# CCM_0022.net
KiCad netlist of a schematic drawn in EAGLE
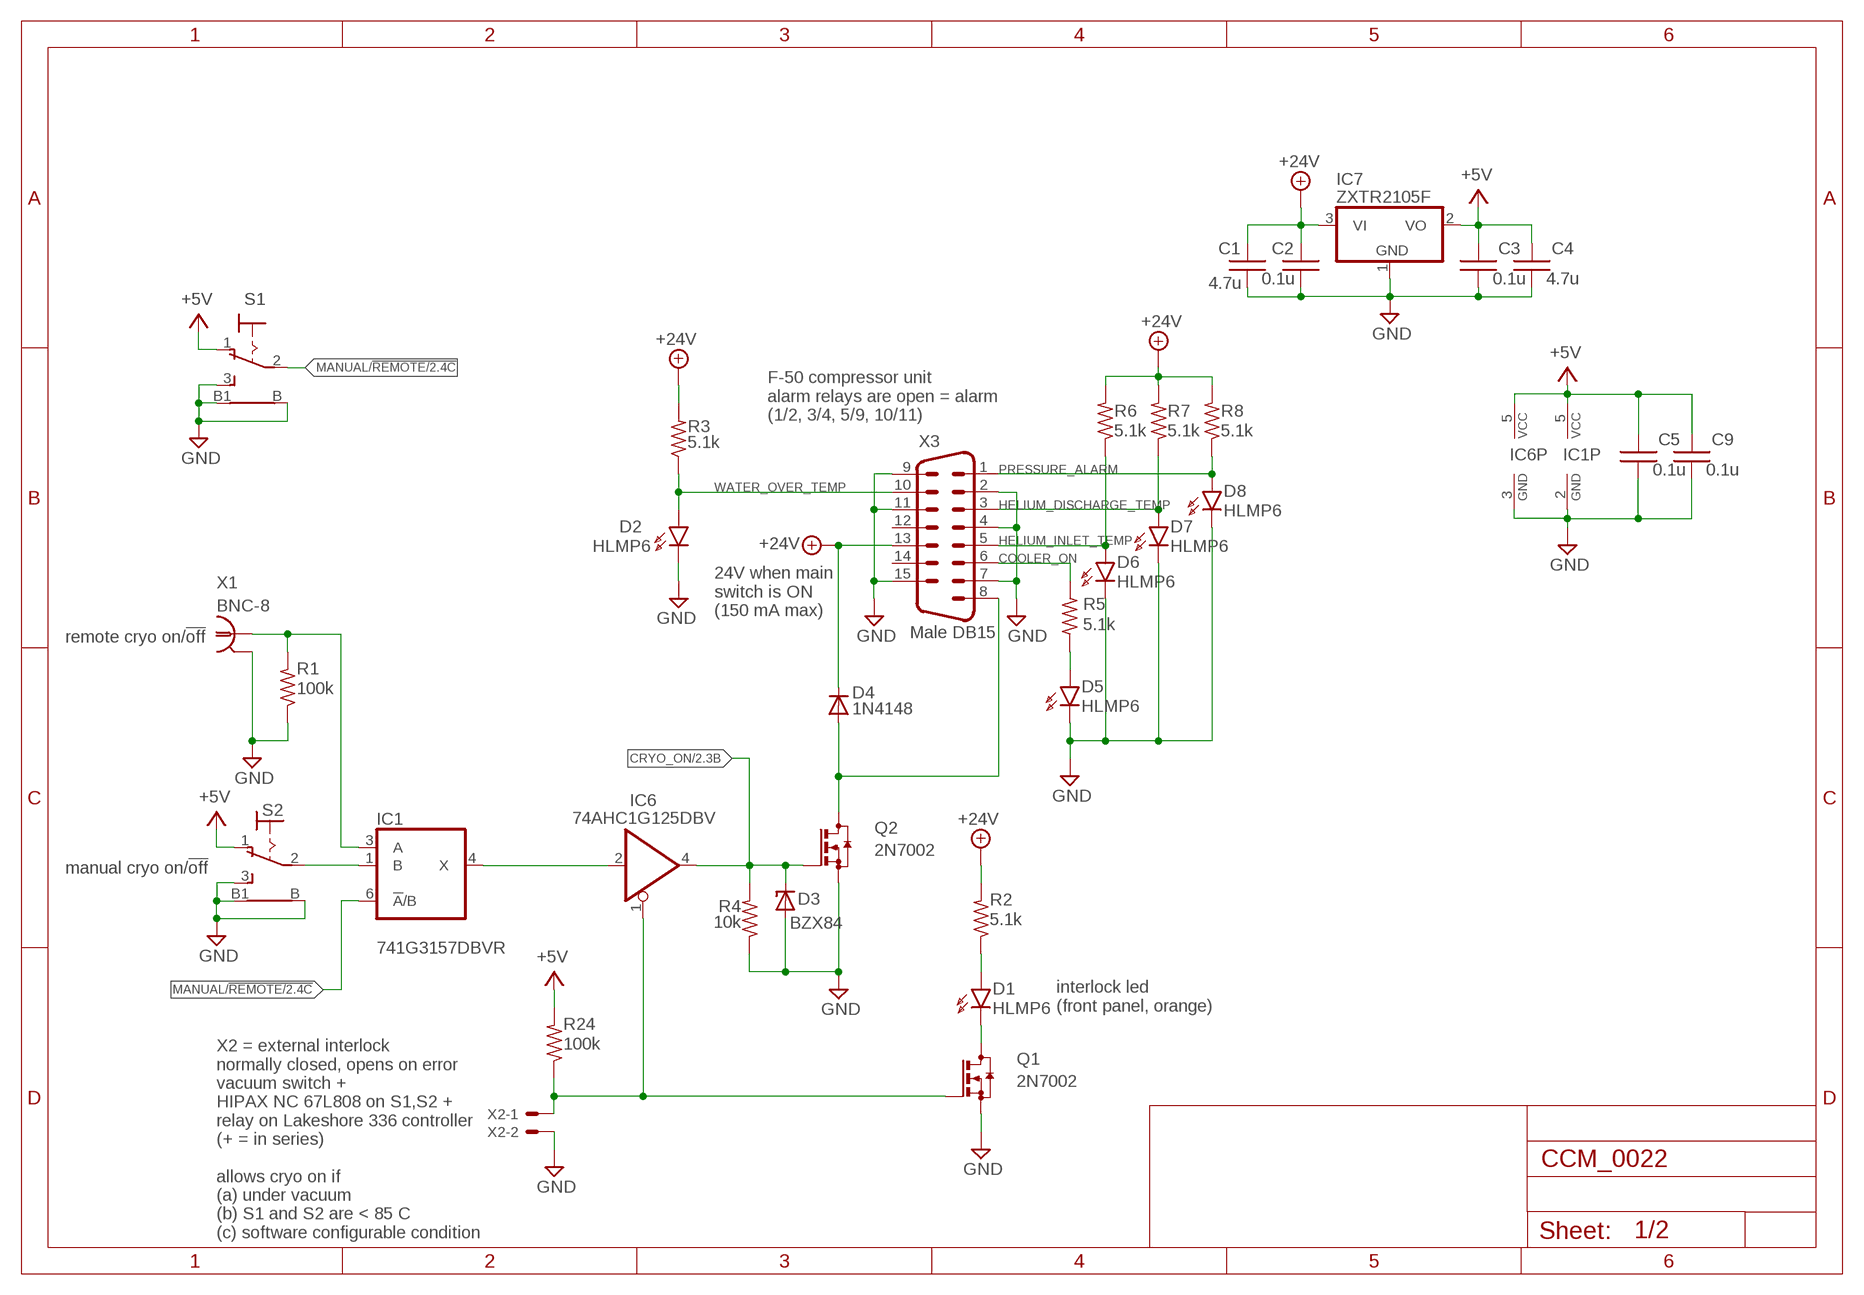
[diagram p0: schematic, sheet 1]
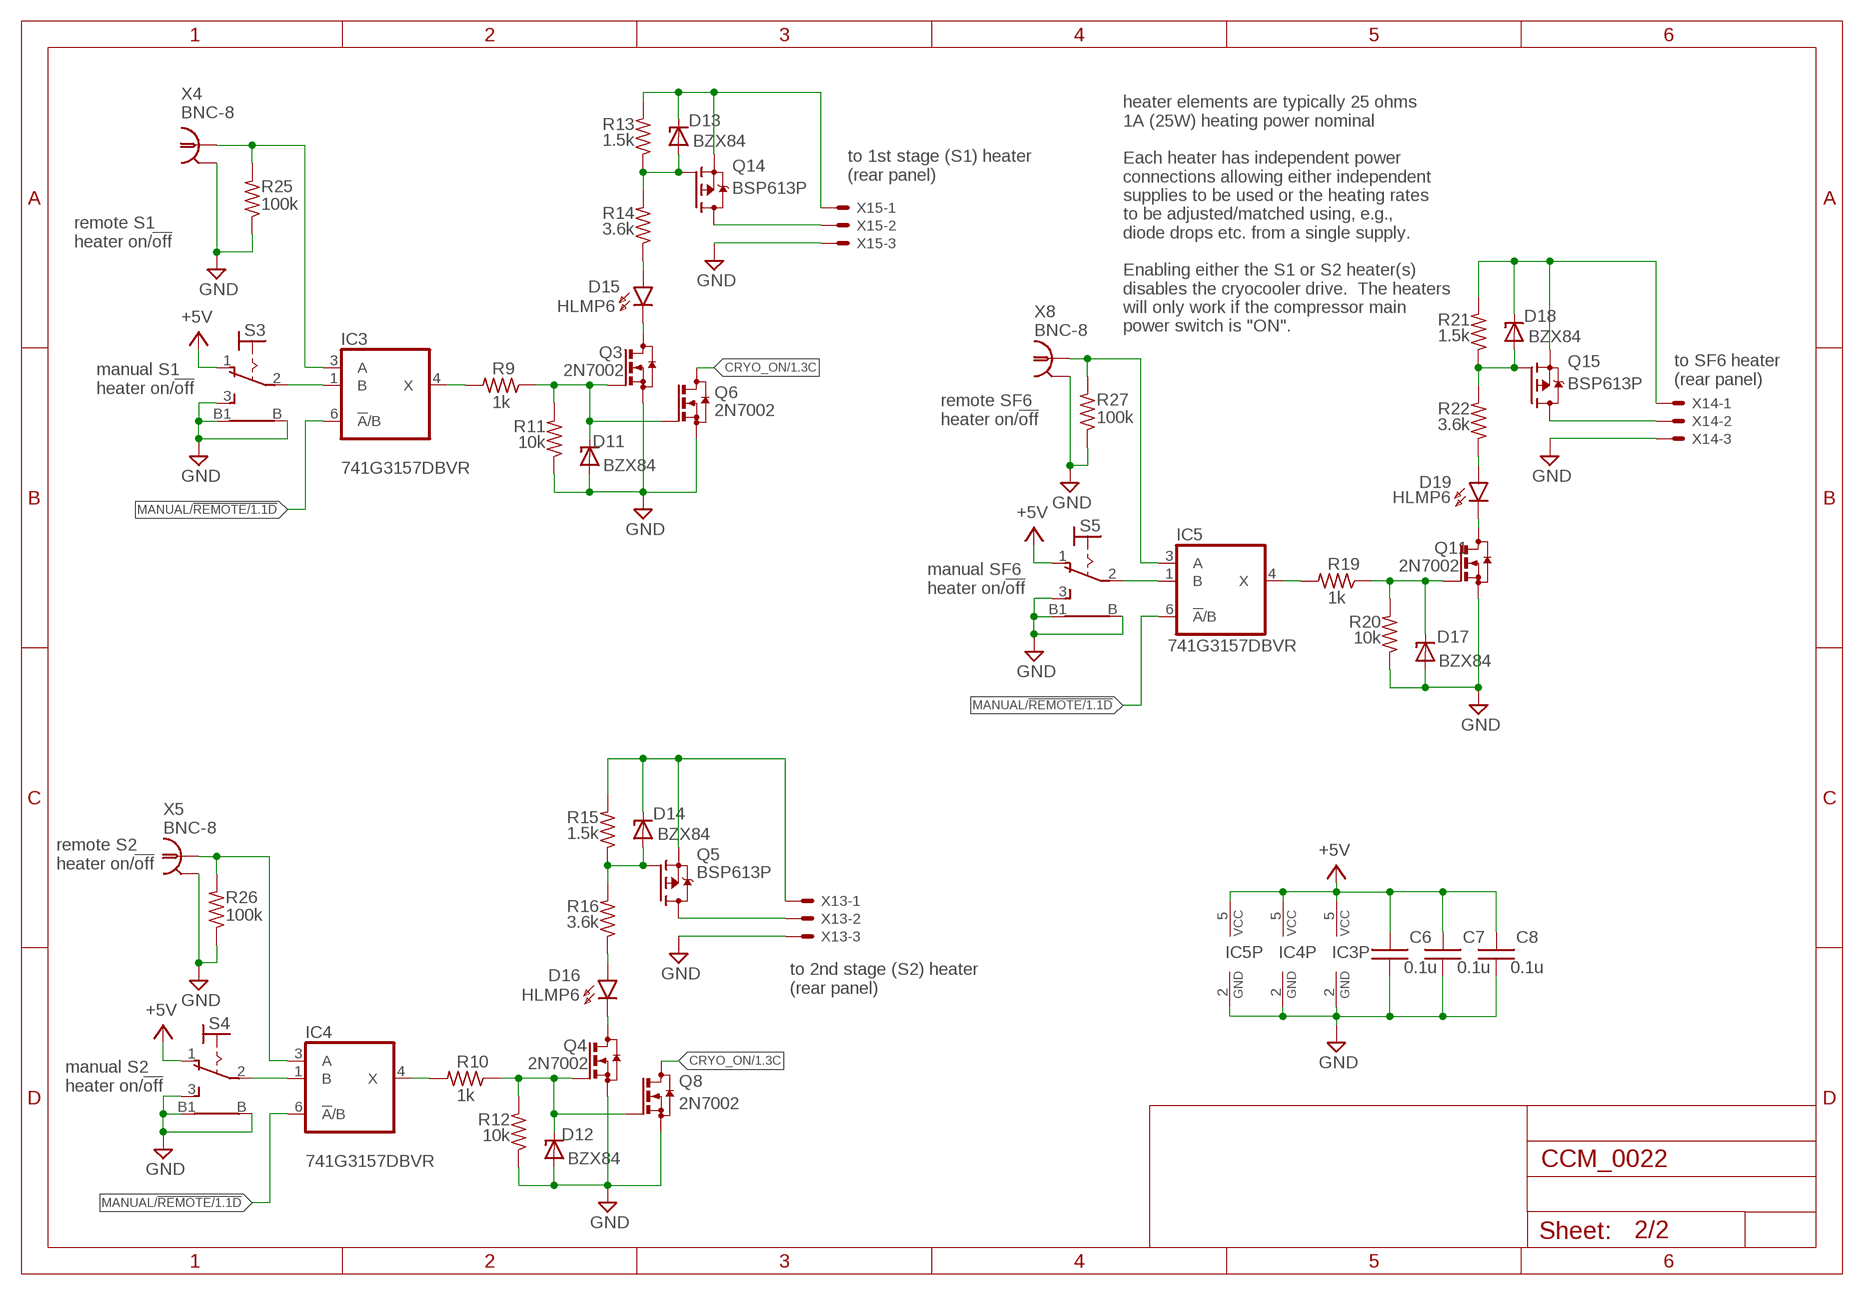
[diagram p1: schematic, sheet 2]

(export (version "E")
  (design (tool "Eeschema 10.0.6"))
  (components
    (comp (ref "C1")
      (value "4.7u")
      (footprint "eagle-import:0603")
      (libsource (lib "eagle-import") (part "CAPACITOR0603"))
    )
    (comp (ref "C2")
      (value "0.1u")
      (footprint "eagle-import:0603")
      (libsource (lib "eagle-import") (part "CAPACITOR0603"))
    )
    (comp (ref "C3")
      (value "0.1u")
      (footprint "eagle-import:0603")
      (libsource (lib "eagle-import") (part "CAPACITOR0603"))
    )
    (comp (ref "C4")
      (value "4.7u")
      (footprint "eagle-import:0603")
      (libsource (lib "eagle-import") (part "CAPACITOR0603"))
    )
    (comp (ref "C5")
      (value "0.1u")
      (footprint "eagle-import:0603")
      (libsource (lib "eagle-import") (part "CAPACITOR0603"))
    )
    (comp (ref "C9")
      (value "0.1u")
      (footprint "eagle-import:0603")
      (libsource (lib "eagle-import") (part "CAPACITOR0603"))
    )
    (comp (ref "D1")
      (value "HLMP6")
      (footprint "eagle-import:HLMP6")
      (fields (field (name "MF") "AGILENT TECHNOLOGIES") (field (name "MPN") "HLMP-6500"))
      (libsource (lib "eagle-import") (part "HLMP6"))
    )
    (comp (ref "D2")
      (value "HLMP6")
      (footprint "eagle-import:HLMP6")
      (fields (field (name "MF") "AGILENT TECHNOLOGIES") (field (name "MPN") "HLMP-6500"))
      (libsource (lib "eagle-import") (part "HLMP6"))
    )
    (comp (ref "D3")
      (value "BZX84")
      (footprint "eagle-import:TO236")
      (libsource (lib "eagle-import") (part "BZX84CSMD"))
    )
    (comp (ref "D4")
      (value "1N4148")
      (footprint "eagle-import:SOD323-W")
      (libsource (lib "eagle-import") (part "DIODE-SOD323-W"))
    )
    (comp (ref "D5")
      (value "HLMP6")
      (footprint "eagle-import:HLMP6")
      (fields (field (name "MF") "AGILENT TECHNOLOGIES") (field (name "MPN") "HLMP-6500"))
      (libsource (lib "eagle-import") (part "HLMP6"))
    )
    (comp (ref "D6")
      (value "HLMP6")
      (footprint "eagle-import:HLMP6")
      (fields (field (name "MF") "AGILENT TECHNOLOGIES") (field (name "MPN") "HLMP-6500"))
      (libsource (lib "eagle-import") (part "HLMP6"))
    )
    (comp (ref "D7")
      (value "HLMP6")
      (footprint "eagle-import:HLMP6")
      (fields (field (name "MF") "AGILENT TECHNOLOGIES") (field (name "MPN") "HLMP-6500"))
      (libsource (lib "eagle-import") (part "HLMP6"))
    )
    (comp (ref "D8")
      (value "HLMP6")
      (footprint "eagle-import:HLMP6")
      (fields (field (name "MF") "AGILENT TECHNOLOGIES") (field (name "MPN") "HLMP-6500"))
      (libsource (lib "eagle-import") (part "HLMP6"))
    )
    (comp (ref "IC1")
      (value "741G3157DBVR")
      (footprint "eagle-import:DBV_R-PDSO-G6")
      (libsource (lib "eagle-import") (part "741G3157DBVR"))
    )
    (comp (ref "IC6")
      (value "74AHC1G125DBV")
      (footprint "eagle-import:SOT23-5")
      (libsource (lib "eagle-import") (part "741G125DBVAHC"))
    )
    (comp (ref "IC7")
      (value "ZXTR2105F")
      (footprint "eagle-import:SOT23")
      (libsource (lib "eagle-import") (part "MCP1703CB"))
    )
    (comp (ref "Q1")
      (value "2N7002")
      (footprint "eagle-import:SOT23")
      (libsource (lib "eagle-import") (part "BSS123"))
    )
    (comp (ref "Q2")
      (value "2N7002")
      (footprint "eagle-import:SOT23")
      (libsource (lib "eagle-import") (part "BSS123"))
    )
    (comp (ref "R1")
      (value "100k")
      (footprint "eagle-import:0603")
      (libsource (lib "eagle-import") (part "R0603"))
    )
    (comp (ref "R2")
      (value "5.1k")
      (footprint "eagle-import:0603")
      (libsource (lib "eagle-import") (part "R0603"))
    )
    (comp (ref "R3")
      (value "5.1k")
      (footprint "eagle-import:0603")
      (libsource (lib "eagle-import") (part "R0603"))
    )
    (comp (ref "R4")
      (value "10k")
      (footprint "eagle-import:0603")
      (libsource (lib "eagle-import") (part "R0603"))
    )
    (comp (ref "R5")
      (value "5.1k")
      (footprint "eagle-import:0603")
      (libsource (lib "eagle-import") (part "R0603"))
    )
    (comp (ref "R6")
      (value "5.1k")
      (footprint "eagle-import:0603")
      (libsource (lib "eagle-import") (part "R0603"))
    )
    (comp (ref "R7")
      (value "5.1k")
      (footprint "eagle-import:0603")
      (libsource (lib "eagle-import") (part "R0603"))
    )
    (comp (ref "R8")
      (value "5.1k")
      (footprint "eagle-import:0603")
      (libsource (lib "eagle-import") (part "R0603"))
    )
    (comp (ref "R24")
      (value "100k")
      (footprint "eagle-import:0603")
      (libsource (lib "eagle-import") (part "R0603"))
    )
    (comp (ref "S1")
      (value "LPV-1")
      (footprint "eagle-import:LPV-1")
      (libsource (lib "eagle-import") (part "LPV-1"))
    )
    (comp (ref "S2")
      (value "LPV-1")
      (footprint "eagle-import:LPV-1")
      (libsource (lib "eagle-import") (part "LPV-1"))
    )
    (comp (ref "X1")
      (value "BNC-8")
      (footprint "eagle-import:BNC_RA")
      (libsource (lib "eagle-import") (part "BNC-8"))
    )
    (comp (ref "X2")
      (value "22-23-2021")
      (footprint "eagle-import:22-23-2021")
      (fields (field (name "MF") "MOLEX"))
      (libsource (lib "eagle-import") (part "22-23-2021"))
    )
    (comp (ref "X3")
      (value "Male DB15")
      (footprint "eagle-import:M15HP")
      (libsource (lib "eagle-import") (part "M15HP"))
    )
    (comp (ref "C6")
      (value "0.1u")
      (footprint "eagle-import:0603")
      (libsource (lib "eagle-import") (part "CAPACITOR0603"))
    )
    (comp (ref "C7")
      (value "0.1u")
      (footprint "eagle-import:0603")
      (libsource (lib "eagle-import") (part "CAPACITOR0603"))
    )
    (comp (ref "C8")
      (value "0.1u")
      (footprint "eagle-import:0603")
      (libsource (lib "eagle-import") (part "CAPACITOR0603"))
    )
    (comp (ref "D11")
      (value "BZX84")
      (footprint "eagle-import:TO236")
      (libsource (lib "eagle-import") (part "BZX84CSMD"))
    )
    (comp (ref "D12")
      (value "BZX84")
      (footprint "eagle-import:TO236")
      (libsource (lib "eagle-import") (part "BZX84CSMD"))
    )
    (comp (ref "D13")
      (value "BZX84")
      (footprint "eagle-import:TO236")
      (libsource (lib "eagle-import") (part "BZX84CSMD"))
    )
    (comp (ref "D14")
      (value "BZX84")
      (footprint "eagle-import:TO236")
      (libsource (lib "eagle-import") (part "BZX84CSMD"))
    )
    (comp (ref "D15")
      (value "HLMP6")
      (footprint "eagle-import:HLMP6")
      (fields (field (name "MF") "AGILENT TECHNOLOGIES") (field (name "MPN") "HLMP-6500"))
      (libsource (lib "eagle-import") (part "HLMP6"))
    )
    (comp (ref "D16")
      (value "HLMP6")
      (footprint "eagle-import:HLMP6")
      (fields (field (name "MF") "AGILENT TECHNOLOGIES") (field (name "MPN") "HLMP-6500"))
      (libsource (lib "eagle-import") (part "HLMP6"))
    )
    (comp (ref "D17")
      (value "BZX84")
      (footprint "eagle-import:TO236")
      (libsource (lib "eagle-import") (part "BZX84CSMD"))
    )
    (comp (ref "D18")
      (value "BZX84")
      (footprint "eagle-import:TO236")
      (libsource (lib "eagle-import") (part "BZX84CSMD"))
    )
    (comp (ref "D19")
      (value "HLMP6")
      (footprint "eagle-import:HLMP6")
      (fields (field (name "MF") "AGILENT TECHNOLOGIES") (field (name "MPN") "HLMP-6500"))
      (libsource (lib "eagle-import") (part "HLMP6"))
    )
    (comp (ref "IC3")
      (value "741G3157DBVR")
      (footprint "eagle-import:DBV_R-PDSO-G6")
      (libsource (lib "eagle-import") (part "741G3157DBVR"))
    )
    (comp (ref "IC4")
      (value "741G3157DBVR")
      (footprint "eagle-import:DBV_R-PDSO-G6")
      (libsource (lib "eagle-import") (part "741G3157DBVR"))
    )
    (comp (ref "IC5")
      (value "741G3157DBVR")
      (footprint "eagle-import:DBV_R-PDSO-G6")
      (libsource (lib "eagle-import") (part "741G3157DBVR"))
    )
    (comp (ref "Q3")
      (value "2N7002")
      (footprint "eagle-import:SOT23")
      (libsource (lib "eagle-import") (part "BSS123"))
    )
    (comp (ref "Q4")
      (value "2N7002")
      (footprint "eagle-import:SOT23")
      (libsource (lib "eagle-import") (part "BSS123"))
    )
    (comp (ref "Q5")
      (value "BSP613P")
      (footprint "eagle-import:SOT223")
      (libsource (lib "eagle-import") (part "BSP170P"))
    )
    (comp (ref "Q6")
      (value "2N7002")
      (footprint "eagle-import:SOT23")
      (libsource (lib "eagle-import") (part "BSS123"))
    )
    (comp (ref "Q8")
      (value "2N7002")
      (footprint "eagle-import:SOT23")
      (libsource (lib "eagle-import") (part "BSS123"))
    )
    (comp (ref "Q11")
      (value "2N7002")
      (footprint "eagle-import:SOT23")
      (libsource (lib "eagle-import") (part "BSS123"))
    )
    (comp (ref "Q14")
      (value "BSP613P")
      (footprint "eagle-import:SOT223")
      (libsource (lib "eagle-import") (part "BSP170P"))
    )
    (comp (ref "Q15")
      (value "BSP613P")
      (footprint "eagle-import:SOT223")
      (libsource (lib "eagle-import") (part "BSP170P"))
    )
    (comp (ref "R9")
      (value "1k")
      (footprint "eagle-import:0603")
      (libsource (lib "eagle-import") (part "R0603"))
    )
    (comp (ref "R10")
      (value "1k")
      (footprint "eagle-import:0603")
      (libsource (lib "eagle-import") (part "R0603"))
    )
    (comp (ref "R11")
      (value "10k")
      (footprint "eagle-import:0603")
      (libsource (lib "eagle-import") (part "R0603"))
    )
    (comp (ref "R12")
      (value "10k")
      (footprint "eagle-import:0603")
      (libsource (lib "eagle-import") (part "R0603"))
    )
    (comp (ref "R13")
      (value "1.5k")
      (footprint "eagle-import:0603")
      (libsource (lib "eagle-import") (part "R0603"))
    )
    (comp (ref "R14")
      (value "3.6k")
      (footprint "eagle-import:0603")
      (libsource (lib "eagle-import") (part "R0603"))
    )
    (comp (ref "R15")
      (value "1.5k")
      (footprint "eagle-import:0603")
      (libsource (lib "eagle-import") (part "R0603"))
    )
    (comp (ref "R16")
      (value "3.6k")
      (footprint "eagle-import:0603")
      (libsource (lib "eagle-import") (part "R0603"))
    )
    (comp (ref "R19")
      (value "1k")
      (footprint "eagle-import:0603")
      (libsource (lib "eagle-import") (part "R0603"))
    )
    (comp (ref "R20")
      (value "10k")
      (footprint "eagle-import:0603")
      (libsource (lib "eagle-import") (part "R0603"))
    )
    (comp (ref "R21")
      (value "1.5k")
      (footprint "eagle-import:0603")
      (libsource (lib "eagle-import") (part "R0603"))
    )
    (comp (ref "R22")
      (value "3.6k")
      (footprint "eagle-import:0603")
      (libsource (lib "eagle-import") (part "R0603"))
    )
    (comp (ref "R25")
      (value "100k")
      (footprint "eagle-import:0603")
      (libsource (lib "eagle-import") (part "R0603"))
    )
    (comp (ref "R26")
      (value "100k")
      (footprint "eagle-import:0603")
      (libsource (lib "eagle-import") (part "R0603"))
    )
    (comp (ref "R27")
      (value "100k")
      (footprint "eagle-import:0603")
      (libsource (lib "eagle-import") (part "R0603"))
    )
    (comp (ref "S3")
      (value "LPV-1")
      (footprint "eagle-import:LPV-1")
      (libsource (lib "eagle-import") (part "LPV-1"))
    )
    (comp (ref "S4")
      (value "LPV-1")
      (footprint "eagle-import:LPV-1")
      (libsource (lib "eagle-import") (part "LPV-1"))
    )
    (comp (ref "S5")
      (value "LPV-1")
      (footprint "eagle-import:LPV-1")
      (libsource (lib "eagle-import") (part "LPV-1"))
    )
    (comp (ref "X4")
      (value "BNC-8")
      (footprint "eagle-import:BNC_RA")
      (libsource (lib "eagle-import") (part "BNC-8"))
    )
    (comp (ref "X5")
      (value "BNC-8")
      (footprint "eagle-import:BNC_RA")
      (libsource (lib "eagle-import") (part "BNC-8"))
    )
    (comp (ref "X8")
      (value "BNC-8")
      (footprint "eagle-import:BNC_RA")
      (libsource (lib "eagle-import") (part "BNC-8"))
    )
    (comp (ref "X13")
      (value "22-23-2031")
      (footprint "eagle-import:22-23-2031")
      (fields (field (name "MF") "MOLEX"))
      (libsource (lib "eagle-import") (part "22-23-2031"))
    )
    (comp (ref "X14")
      (value "22-23-2031")
      (footprint "eagle-import:22-23-2031")
      (fields (field (name "MF") "MOLEX"))
      (libsource (lib "eagle-import") (part "22-23-2031"))
    )
    (comp (ref "X15")
      (value "22-23-2031")
      (footprint "eagle-import:22-23-2031")
      (fields (field (name "MF") "MOLEX"))
      (libsource (lib "eagle-import") (part "22-23-2031"))
    )
  )
  (nets
    (net (code "1") (name "+5V") (class "Default")
      (node (ref "C3") (pin "1") (pinfunction "1_1") (pintype "passive"))
      (node (ref "C4") (pin "1") (pinfunction "1_1") (pintype "passive"))
      (node (ref "C5") (pin "1") (pinfunction "1_1") (pintype "passive"))
      (node (ref "C6") (pin "1") (pinfunction "1_1") (pintype "passive"))
      (node (ref "C7") (pin "1") (pinfunction "1_1") (pintype "passive"))
      (node (ref "C8") (pin "1") (pinfunction "1_1") (pintype "passive"))
      (node (ref "C9") (pin "1") (pinfunction "1_1") (pintype "passive"))
      (node (ref "IC1") (pin "5") (pinfunction "VCC_5") (pintype "power_in"))
      (node (ref "IC3") (pin "5") (pinfunction "VCC_5") (pintype "power_in"))
      (node (ref "IC4") (pin "5") (pinfunction "VCC_5") (pintype "power_in"))
      (node (ref "IC5") (pin "5") (pinfunction "VCC_5") (pintype "power_in"))
      (node (ref "IC6") (pin "5") (pinfunction "VCC_5") (pintype "power_in"))
      (node (ref "IC7") (pin "2") (pinfunction "VO_2") (pintype "passive"))
      (node (ref "R24") (pin "2") (pinfunction "2_2") (pintype "passive"))
      (node (ref "S1") (pin "1") (pinfunction "O_1") (pintype "passive"))
      (node (ref "S2") (pin "1") (pinfunction "O_1") (pintype "passive"))
      (node (ref "S3") (pin "1") (pinfunction "O_1") (pintype "passive"))
      (node (ref "S4") (pin "1") (pinfunction "O_1") (pintype "passive"))
      (node (ref "S5") (pin "1") (pinfunction "O_1") (pintype "passive"))
    )
    (net (code "2") (name "+24V") (class "Default")
      (node (ref "C1") (pin "1") (pinfunction "1_1") (pintype "passive"))
      (node (ref "C2") (pin "1") (pinfunction "1_1") (pintype "passive"))
      (node (ref "D4") (pin "C") (pinfunction "C_C") (pintype "passive"))
      (node (ref "IC7") (pin "3") (pinfunction "VI_3") (pintype "input"))
      (node (ref "R2") (pin "2") (pinfunction "2_2") (pintype "passive"))
      (node (ref "R3") (pin "2") (pinfunction "2_2") (pintype "passive"))
      (node (ref "R6") (pin "2") (pinfunction "2_2") (pintype "passive"))
      (node (ref "R7") (pin "2") (pinfunction "2_2") (pintype "passive"))
      (node (ref "R8") (pin "2") (pinfunction "2_2") (pintype "passive"))
      (node (ref "X3") (pin "13") (pinfunction "13_13") (pintype "passive"))
    )
    (net (code "3") (name "COOLER_ON") (class "Default")
      (node (ref "R5") (pin "2") (pinfunction "2_2") (pintype "passive"))
      (node (ref "X3") (pin "6") (pinfunction "6_6") (pintype "passive"))
    )
    (net (code "4") (name "CRYO_ON") (class "Default")
      (node (ref "D3") (pin "C") (pinfunction "C_C") (pintype "passive"))
      (node (ref "IC6") (pin "4") (pinfunction "O_4") (pintype "tri_state"))
      (node (ref "Q2") (pin "1") (pinfunction "G_1") (pintype "passive"))
      (node (ref "Q6") (pin "3") (pinfunction "D_3") (pintype "passive"))
      (node (ref "Q8") (pin "3") (pinfunction "D_3") (pintype "passive"))
      (node (ref "R4") (pin "2") (pinfunction "2_2") (pintype "passive"))
    )
    (net (code "5") (name "GND") (class "Default")
      (node (ref "C1") (pin "2") (pinfunction "2_2") (pintype "passive"))
      (node (ref "C2") (pin "2") (pinfunction "2_2") (pintype "passive"))
      (node (ref "C3") (pin "2") (pinfunction "2_2") (pintype "passive"))
      (node (ref "C4") (pin "2") (pinfunction "2_2") (pintype "passive"))
      (node (ref "C5") (pin "2") (pinfunction "2_2") (pintype "passive"))
      (node (ref "C6") (pin "2") (pinfunction "2_2") (pintype "passive"))
      (node (ref "C7") (pin "2") (pinfunction "2_2") (pintype "passive"))
      (node (ref "C8") (pin "2") (pinfunction "2_2") (pintype "passive"))
      (node (ref "C9") (pin "2") (pinfunction "2_2") (pintype "passive"))
      (node (ref "D11") (pin "A") (pinfunction "A_A") (pintype "passive"))
      (node (ref "D12") (pin "A") (pinfunction "A_A") (pintype "passive"))
      (node (ref "D17") (pin "A") (pinfunction "A_A") (pintype "passive"))
      (node (ref "D2") (pin "K") (pinfunction "K_K") (pintype "passive"))
      (node (ref "D3") (pin "A") (pinfunction "A_A") (pintype "passive"))
      (node (ref "D5") (pin "K") (pinfunction "K_K") (pintype "passive"))
      (node (ref "D6") (pin "K") (pinfunction "K_K") (pintype "passive"))
      (node (ref "D7") (pin "K") (pinfunction "K_K") (pintype "passive"))
      (node (ref "D8") (pin "K") (pinfunction "K_K") (pintype "passive"))
      (node (ref "IC1") (pin "2") (pinfunction "GND_2") (pintype "power_in"))
      (node (ref "IC3") (pin "2") (pinfunction "GND_2") (pintype "power_in"))
      (node (ref "IC4") (pin "2") (pinfunction "GND_2") (pintype "power_in"))
      (node (ref "IC5") (pin "2") (pinfunction "GND_2") (pintype "power_in"))
      (node (ref "IC6") (pin "3") (pinfunction "GND_3") (pintype "power_in"))
      (node (ref "IC7") (pin "1") (pinfunction "GND_1") (pintype "passive"))
      (node (ref "Q1") (pin "2") (pinfunction "S_2") (pintype "passive"))
      (node (ref "Q11") (pin "2") (pinfunction "S_2") (pintype "passive"))
      (node (ref "Q2") (pin "2") (pinfunction "S_2") (pintype "passive"))
      (node (ref "Q3") (pin "2") (pinfunction "S_2") (pintype "passive"))
      (node (ref "Q4") (pin "2") (pinfunction "S_2") (pintype "passive"))
      (node (ref "Q6") (pin "2") (pinfunction "S_2") (pintype "passive"))
      (node (ref "Q8") (pin "2") (pinfunction "S_2") (pintype "passive"))
      (node (ref "R1") (pin "1") (pinfunction "1_1") (pintype "passive"))
      (node (ref "R11") (pin "1") (pinfunction "1_1") (pintype "passive"))
      (node (ref "R12") (pin "1") (pinfunction "1_1") (pintype "passive"))
      (node (ref "R20") (pin "1") (pinfunction "1_1") (pintype "passive"))
      (node (ref "R25") (pin "1") (pinfunction "1_1") (pintype "passive"))
      (node (ref "R26") (pin "1") (pinfunction "1_1") (pintype "passive"))
      (node (ref "R27") (pin "1") (pinfunction "1_1") (pintype "passive"))
      (node (ref "R4") (pin "1") (pinfunction "1_1") (pintype "passive"))
      (node (ref "S1") (pin "3") (pinfunction "S_3") (pintype "passive"))
      (node (ref "S1") (pin "B") (pinfunction "B_B") (pintype "passive"))
      (node (ref "S1") (pin "B1") (pinfunction "B1_B1") (pintype "passive"))
      (node (ref "S2") (pin "3") (pinfunction "S_3") (pintype "passive"))
      (node (ref "S2") (pin "B") (pinfunction "B_B") (pintype "passive"))
      (node (ref "S2") (pin "B1") (pinfunction "B1_B1") (pintype "passive"))
      (node (ref "S3") (pin "3") (pinfunction "S_3") (pintype "passive"))
      (node (ref "S3") (pin "B") (pinfunction "B_B") (pintype "passive"))
      (node (ref "S3") (pin "B1") (pinfunction "B1_B1") (pintype "passive"))
      (node (ref "S4") (pin "3") (pinfunction "S_3") (pintype "passive"))
      (node (ref "S4") (pin "B") (pinfunction "B_B") (pintype "passive"))
      (node (ref "S4") (pin "B1") (pinfunction "B1_B1") (pintype "passive"))
      (node (ref "S5") (pin "3") (pinfunction "S_3") (pintype "passive"))
      (node (ref "S5") (pin "B") (pinfunction "B_B") (pintype "passive"))
      (node (ref "S5") (pin "B1") (pinfunction "B1_B1") (pintype "passive"))
      (node (ref "X1") (pin "2") (pinfunction "2_2") (pintype "passive"))
      (node (ref "X13") (pin "3") (pinfunction "S_3") (pintype "passive"))
      (node (ref "X14") (pin "3") (pinfunction "S_3") (pintype "passive"))
      (node (ref "X15") (pin "3") (pinfunction "S_3") (pintype "passive"))
      (node (ref "X2") (pin "2") (pinfunction "S_2") (pintype "passive"))
      (node (ref "X3") (pin "11") (pinfunction "11_11") (pintype "passive"))
      (node (ref "X3") (pin "15") (pinfunction "15_15") (pintype "passive"))
      (node (ref "X3") (pin "2") (pinfunction "2_2") (pintype "passive"))
      (node (ref "X3") (pin "4") (pinfunction "4_4") (pintype "passive"))
      (node (ref "X3") (pin "7") (pinfunction "7_7") (pintype "passive"))
      (node (ref "X3") (pin "9") (pinfunction "9_9") (pintype "passive"))
      (node (ref "X4") (pin "2") (pinfunction "2_2") (pintype "passive"))
      (node (ref "X5") (pin "2") (pinfunction "2_2") (pintype "passive"))
      (node (ref "X8") (pin "2") (pinfunction "2_2") (pintype "passive"))
    )
    (net (code "6") (name "HELIUM_DISCHARGE_TEMP") (class "Default")
      (node (ref "D7") (pin "A") (pinfunction "A_A") (pintype "passive"))
      (node (ref "R7") (pin "1") (pinfunction "1_1") (pintype "passive"))
      (node (ref "X3") (pin "3") (pinfunction "3_3") (pintype "passive"))
    )
    (net (code "7") (name "HELIUM_INLET_TEMP") (class "Default")
      (node (ref "D6") (pin "A") (pinfunction "A_A") (pintype "passive"))
      (node (ref "R6") (pin "1") (pinfunction "1_1") (pintype "passive"))
      (node (ref "X3") (pin "5") (pinfunction "5_5") (pintype "passive"))
    )
    (net (code "8") (name "MANUAL{slash}~{REMOTE}") (class "Default")
      (node (ref "IC1") (pin "6") (pinfunction "~{A}/B_6") (pintype "input"))
      (node (ref "IC3") (pin "6") (pinfunction "~{A}/B_6") (pintype "input"))
      (node (ref "IC4") (pin "6") (pinfunction "~{A}/B_6") (pintype "input"))
      (node (ref "IC5") (pin "6") (pinfunction "~{A}/B_6") (pintype "input"))
      (node (ref "S1") (pin "2") (pinfunction "P_2") (pintype "passive"))
    )
    (net (code "9") (name "Net-(D1-PadA)") (class "Default")
      (node (ref "D1") (pin "A") (pinfunction "A_A") (pintype "passive"))
      (node (ref "R2") (pin "1") (pinfunction "1_1") (pintype "passive"))
    )
    (net (code "10") (name "Net-(D5-PadA)") (class "Default")
      (node (ref "D5") (pin "A") (pinfunction "A_A") (pintype "passive"))
      (node (ref "R5") (pin "1") (pinfunction "1_1") (pintype "passive"))
    )
    (net (code "11") (name "Net-(D15-PadA)") (class "Default")
      (node (ref "D15") (pin "A") (pinfunction "A_A") (pintype "passive"))
      (node (ref "R14") (pin "1") (pinfunction "1_1") (pintype "passive"))
    )
    (net (code "12") (name "Net-(D16-PadA)") (class "Default")
      (node (ref "D16") (pin "A") (pinfunction "A_A") (pintype "passive"))
      (node (ref "R16") (pin "1") (pinfunction "1_1") (pintype "passive"))
    )
    (net (code "13") (name "Net-(D19-PadA)") (class "Default")
      (node (ref "D19") (pin "A") (pinfunction "A_A") (pintype "passive"))
      (node (ref "R22") (pin "1") (pinfunction "1_1") (pintype "passive"))
    )
    (net (code "14") (name "Net-(IC1A-A)") (class "Default")
      (node (ref "IC1") (pin "3") (pinfunction "A_3") (pintype "bidirectional"))
      (node (ref "R1") (pin "2") (pinfunction "2_2") (pintype "passive"))
      (node (ref "X1") (pin "1") (pinfunction "1_1") (pintype "passive"))
    )
    (net (code "15") (name "Net-(IC1A-B)") (class "Default")
      (node (ref "IC1") (pin "1") (pinfunction "B_1") (pintype "bidirectional"))
      (node (ref "S2") (pin "2") (pinfunction "P_2") (pintype "passive"))
    )
    (net (code "16") (name "Net-(IC1A-X)") (class "Default")
      (node (ref "IC1") (pin "4") (pinfunction "X_4") (pintype "bidirectional"))
      (node (ref "IC6") (pin "2") (pinfunction "I_2") (pintype "input"))
    )
    (net (code "17") (name "Net-(IC3A-A)") (class "Default")
      (node (ref "IC3") (pin "3") (pinfunction "A_3") (pintype "bidirectional"))
      (node (ref "R25") (pin "2") (pinfunction "2_2") (pintype "passive"))
      (node (ref "X4") (pin "1") (pinfunction "1_1") (pintype "passive"))
    )
    (net (code "18") (name "Net-(IC3A-B)") (class "Default")
      (node (ref "IC3") (pin "1") (pinfunction "B_1") (pintype "bidirectional"))
      (node (ref "S3") (pin "2") (pinfunction "P_2") (pintype "passive"))
    )
    (net (code "19") (name "Net-(IC3A-X)") (class "Default")
      (node (ref "IC3") (pin "4") (pinfunction "X_4") (pintype "bidirectional"))
      (node (ref "R9") (pin "2") (pinfunction "2_2") (pintype "passive"))
    )
    (net (code "20") (name "Net-(IC4A-A)") (class "Default")
      (node (ref "IC4") (pin "3") (pinfunction "A_3") (pintype "bidirectional"))
      (node (ref "R26") (pin "2") (pinfunction "2_2") (pintype "passive"))
      (node (ref "X5") (pin "1") (pinfunction "1_1") (pintype "passive"))
    )
    (net (code "21") (name "Net-(IC4A-B)") (class "Default")
      (node (ref "IC4") (pin "1") (pinfunction "B_1") (pintype "bidirectional"))
      (node (ref "S4") (pin "2") (pinfunction "P_2") (pintype "passive"))
    )
    (net (code "22") (name "Net-(IC4A-X)") (class "Default")
      (node (ref "IC4") (pin "4") (pinfunction "X_4") (pintype "bidirectional"))
      (node (ref "R10") (pin "2") (pinfunction "2_2") (pintype "passive"))
    )
    (net (code "23") (name "Net-(IC5A-A)") (class "Default")
      (node (ref "IC5") (pin "3") (pinfunction "A_3") (pintype "bidirectional"))
      (node (ref "R27") (pin "2") (pinfunction "2_2") (pintype "passive"))
      (node (ref "X8") (pin "1") (pinfunction "1_1") (pintype "passive"))
    )
    (net (code "24") (name "Net-(IC5A-B)") (class "Default")
      (node (ref "IC5") (pin "1") (pinfunction "B_1") (pintype "bidirectional"))
      (node (ref "S5") (pin "2") (pinfunction "P_2") (pintype "passive"))
    )
    (net (code "25") (name "Net-(IC5A-X)") (class "Default")
      (node (ref "IC5") (pin "4") (pinfunction "X_4") (pintype "bidirectional"))
      (node (ref "R19") (pin "2") (pinfunction "2_2") (pintype "passive"))
    )
    (net (code "26") (name "Net-(IC6A-OE)") (class "Default")
      (node (ref "IC6") (pin "1") (pinfunction "OE_1") (pintype "input"))
      (node (ref "Q1") (pin "1") (pinfunction "G_1") (pintype "passive"))
      (node (ref "R24") (pin "1") (pinfunction "1_1") (pintype "passive"))
      (node (ref "X2") (pin "1") (pinfunction "S_1") (pintype "passive"))
    )
    (net (code "27") (name "Net-(Q1-D)") (class "Default")
      (node (ref "D1") (pin "K") (pinfunction "K_K") (pintype "passive"))
      (node (ref "Q1") (pin "3") (pinfunction "D_3") (pintype "passive"))
    )
    (net (code "28") (name "Net-(Q2-D)") (class "Default")
      (node (ref "D4") (pin "A") (pinfunction "A_A") (pintype "passive"))
      (node (ref "Q2") (pin "3") (pinfunction "D_3") (pintype "passive"))
      (node (ref "X3") (pin "8") (pinfunction "8_8") (pintype "passive"))
    )
    (net (code "29") (name "Net-(Q3-D)") (class "Default")
      (node (ref "D15") (pin "K") (pinfunction "K_K") (pintype "passive"))
      (node (ref "Q3") (pin "3") (pinfunction "D_3") (pintype "passive"))
    )
    (net (code "30") (name "Net-(Q3-G)") (class "Default")
      (node (ref "D11") (pin "C") (pinfunction "C_C") (pintype "passive"))
      (node (ref "Q3") (pin "1") (pinfunction "G_1") (pintype "passive"))
      (node (ref "Q6") (pin "1") (pinfunction "G_1") (pintype "passive"))
      (node (ref "R11") (pin "2") (pinfunction "2_2") (pintype "passive"))
      (node (ref "R9") (pin "1") (pinfunction "1_1") (pintype "passive"))
    )
    (net (code "31") (name "Net-(Q4-D)") (class "Default")
      (node (ref "D16") (pin "K") (pinfunction "K_K") (pintype "passive"))
      (node (ref "Q4") (pin "3") (pinfunction "D_3") (pintype "passive"))
    )
    (net (code "32") (name "Net-(Q4-G)") (class "Default")
      (node (ref "D12") (pin "C") (pinfunction "C_C") (pintype "passive"))
      (node (ref "Q4") (pin "1") (pinfunction "G_1") (pintype "passive"))
      (node (ref "Q8") (pin "1") (pinfunction "G_1") (pintype "passive"))
      (node (ref "R10") (pin "1") (pinfunction "1_1") (pintype "passive"))
      (node (ref "R12") (pin "2") (pinfunction "2_2") (pintype "passive"))
    )
    (net (code "33") (name "Net-(Q5-G)") (class "Default")
      (node (ref "D14") (pin "A") (pinfunction "A_A") (pintype "passive"))
      (node (ref "Q5") (pin "1") (pinfunction "G_1") (pintype "passive"))
      (node (ref "R15") (pin "1") (pinfunction "1_1") (pintype "passive"))
      (node (ref "R16") (pin "2") (pinfunction "2_2") (pintype "passive"))
    )
    (net (code "34") (name "Net-(Q5-S)") (class "Default")
      (node (ref "D14") (pin "C") (pinfunction "C_C") (pintype "passive"))
      (node (ref "Q5") (pin "3") (pinfunction "S_3") (pintype "passive"))
      (node (ref "R15") (pin "2") (pinfunction "2_2") (pintype "passive"))
      (node (ref "X13") (pin "1") (pinfunction "S_1") (pintype "passive"))
    )
    (net (code "35") (name "Net-(Q11-D)") (class "Default")
      (node (ref "D19") (pin "K") (pinfunction "K_K") (pintype "passive"))
      (node (ref "Q11") (pin "3") (pinfunction "D_3") (pintype "passive"))
    )
    (net (code "36") (name "Net-(Q11-G)") (class "Default")
      (node (ref "D17") (pin "C") (pinfunction "C_C") (pintype "passive"))
      (node (ref "Q11") (pin "1") (pinfunction "G_1") (pintype "passive"))
      (node (ref "R19") (pin "1") (pinfunction "1_1") (pintype "passive"))
      (node (ref "R20") (pin "2") (pinfunction "2_2") (pintype "passive"))
    )
    (net (code "37") (name "Net-(Q14-G)") (class "Default")
      (node (ref "D13") (pin "A") (pinfunction "A_A") (pintype "passive"))
      (node (ref "Q14") (pin "1") (pinfunction "G_1") (pintype "passive"))
      (node (ref "R13") (pin "1") (pinfunction "1_1") (pintype "passive"))
      (node (ref "R14") (pin "2") (pinfunction "2_2") (pintype "passive"))
    )
    (net (code "38") (name "Net-(Q14-S)") (class "Default")
      (node (ref "D13") (pin "C") (pinfunction "C_C") (pintype "passive"))
      (node (ref "Q14") (pin "3") (pinfunction "S_3") (pintype "passive"))
      (node (ref "R13") (pin "2") (pinfunction "2_2") (pintype "passive"))
      (node (ref "X15") (pin "1") (pinfunction "S_1") (pintype "passive"))
    )
    (net (code "39") (name "Net-(Q15-G)") (class "Default")
      (node (ref "D18") (pin "A") (pinfunction "A_A") (pintype "passive"))
      (node (ref "Q15") (pin "1") (pinfunction "G_1") (pintype "passive"))
      (node (ref "R21") (pin "1") (pinfunction "1_1") (pintype "passive"))
      (node (ref "R22") (pin "2") (pinfunction "2_2") (pintype "passive"))
    )
    (net (code "40") (name "Net-(Q15-S)") (class "Default")
      (node (ref "D18") (pin "C") (pinfunction "C_C") (pintype "passive"))
      (node (ref "Q15") (pin "3") (pinfunction "S_3") (pintype "passive"))
      (node (ref "R21") (pin "2") (pinfunction "2_2") (pintype "passive"))
      (node (ref "X14") (pin "1") (pinfunction "S_1") (pintype "passive"))
    )
    (net (code "41") (name "Net-(X13B-S)") (class "Default")
      (node (ref "Q5") (pin "2") (pinfunction "D_2") (pintype "passive"))
      (node (ref "Q5") (pin "4") (pinfunction "D_4") (pintype "passive"))
      (node (ref "X13") (pin "2") (pinfunction "S_2") (pintype "passive"))
    )
    (net (code "42") (name "Net-(X14B-S)") (class "Default")
      (node (ref "Q15") (pin "2") (pinfunction "D_2") (pintype "passive"))
      (node (ref "Q15") (pin "4") (pinfunction "D_4") (pintype "passive"))
      (node (ref "X14") (pin "2") (pinfunction "S_2") (pintype "passive"))
    )
    (net (code "43") (name "Net-(X15B-S)") (class "Default")
      (node (ref "Q14") (pin "2") (pinfunction "D_2") (pintype "passive"))
      (node (ref "Q14") (pin "4") (pinfunction "D_4") (pintype "passive"))
      (node (ref "X15") (pin "2") (pinfunction "S_2") (pintype "passive"))
    )
    (net (code "44") (name "PRESSURE_ALARM") (class "Default")
      (node (ref "D8") (pin "A") (pinfunction "A_A") (pintype "passive"))
      (node (ref "R8") (pin "1") (pinfunction "1_1") (pintype "passive"))
      (node (ref "X3") (pin "1") (pinfunction "1_1") (pintype "passive"))
    )
    (net (code "45") (name "WATER_OVER_TEMP") (class "Default")
      (node (ref "D2") (pin "A") (pinfunction "A_A") (pintype "passive"))
      (node (ref "R3") (pin "1") (pinfunction "1_1") (pintype "passive"))
      (node (ref "X3") (pin "10") (pinfunction "10_10") (pintype "passive"))
    )
    (net (code "46") (name "unconnected-(X3-Pad12)") (class "Default")
      (node (ref "X3") (pin "12") (pinfunction "12_12") (pintype "passive"))
    )
    (net (code "47") (name "unconnected-(X3-Pad14)") (class "Default")
      (node (ref "X3") (pin "14") (pinfunction "14_14") (pintype "passive"))
    )
  )
)
